# Sheet1.net
KiCad netlist of a schematic drawn in Altium Designer
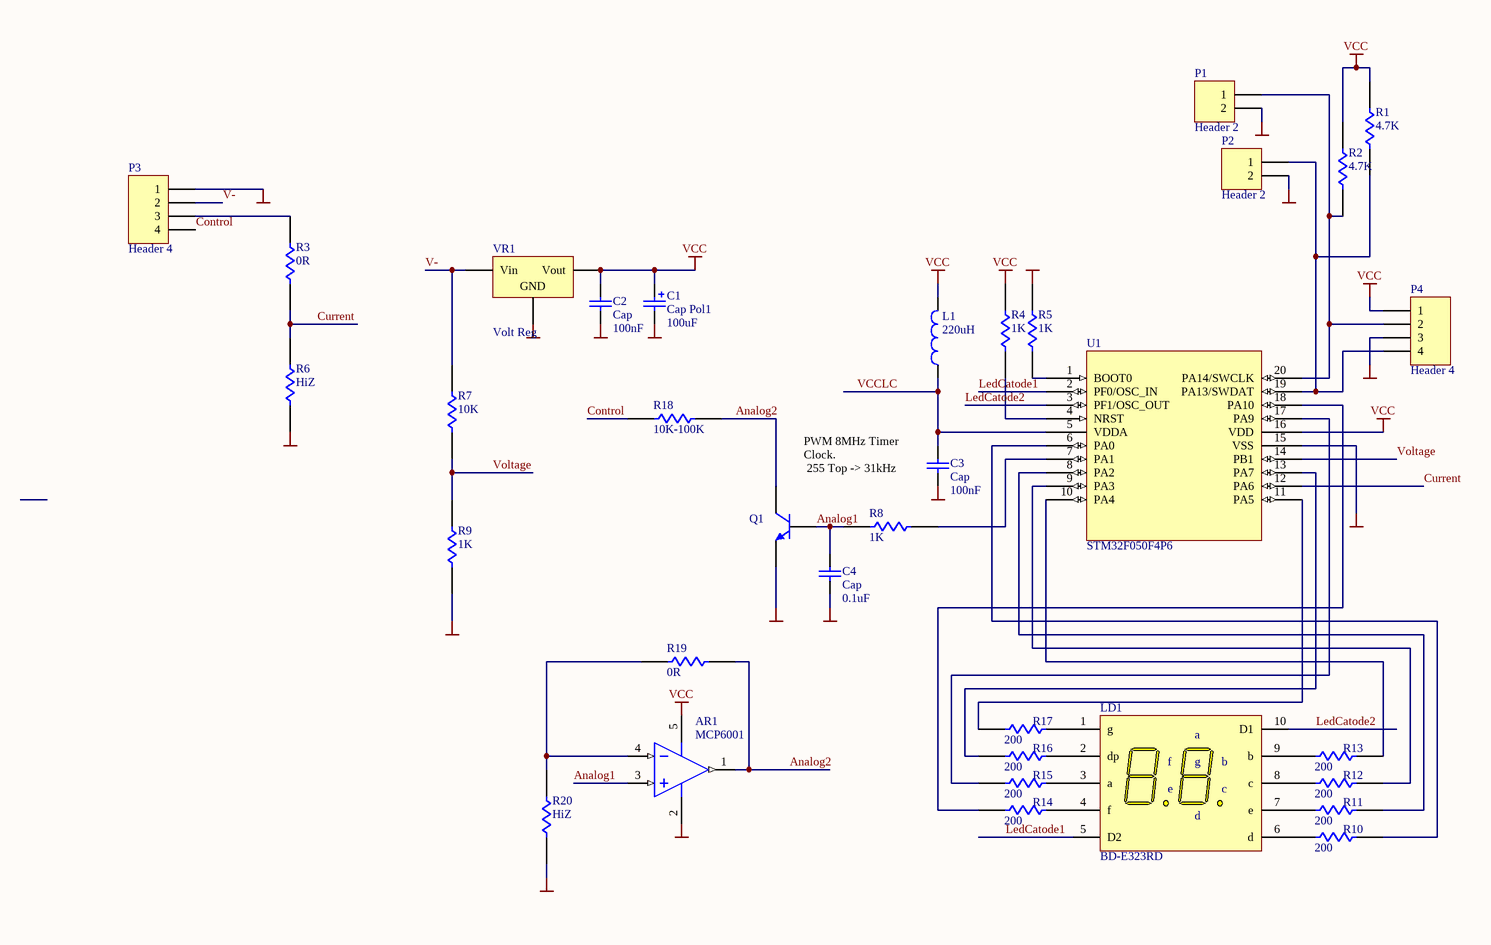
[diagram p0: Sheet1.SchDoc]

(export (version "E")
  (design (tool "Eeschema 10.0.6"))
  (components
    (comp (ref "AR1")
      (value "MCP6001")
      (footprint "SOT23-5_M")
      (description "FET Operational Amplifier")
      (fields (field (name "PUBLISHER") "Altium Limited"))
      (libsource (lib "Project") (part "MCP6001"))
    )
    (comp (ref "C1")
      (value "Cap Pol1")
      (footprint "RAD-0.3")
      (description "Polarized Capacitor (Radial)")
      (fields (field (name "ALTIUM_VALUE") "100uF") (field (name "PUBLISHER") "Altium Limited"))
      (libsource (lib "Project") (part "Cap Pol1"))
    )
    (comp (ref "C2")
      (value "Cap")
      (footprint "6-0805_M")
      (description "Capacitor")
      (fields (field (name "ALTIUM_VALUE") "100nF") (field (name "PUBLISHER") "Altium Limited"))
      (libsource (lib "Project") (part "Cap"))
    )
    (comp (ref "C3")
      (value "Cap")
      (footprint "6-0805_M")
      (description "Capacitor")
      (fields (field (name "ALTIUM_VALUE") "100nF") (field (name "PUBLISHER") "Altium Limited"))
      (libsource (lib "Project") (part "Cap"))
    )
    (comp (ref "C4")
      (value "Cap")
      (footprint "6-0805_M")
      (description "Capacitor")
      (fields (field (name "ALTIUM_VALUE") "0.1uF") (field (name "PUBLISHER") "Altium Limited"))
      (libsource (lib "Project") (part "Cap"))
    )
    (comp (ref "L1")
      (value "220uH")
      (footprint "INDC4532")
      (description "Inductor")
      (fields (field (name "PUBLISHER") "Altium Limited"))
      (libsource (lib "Project") (part "Inductor"))
    )
    (comp (ref "LD1") (value "BD-E323RD") (footprint "DD-04") (libsource (lib "Project") (part "BD-E323RD")))
    (comp (ref "P1")
      (value "Header 2")
      (footprint "HDR1X2")
      (description "Header, 2-Pin")
      (fields (field (name "PUBLISHER") "Altium Limited"))
      (libsource (lib "Miscellaneous Connectors") (part "Header 2"))
    )
    (comp (ref "P2")
      (value "Header 2")
      (footprint "HDR1X2")
      (description "Header, 2-Pin")
      (fields (field (name "PUBLISHER") "Altium Limited"))
      (libsource (lib "Miscellaneous Connectors") (part "Header 2"))
    )
    (comp (ref "P3")
      (value "Header 4")
      (footprint "HDR1X4")
      (description "Header, 4-Pin")
      (fields (field (name "PUBLISHER") "Altium Limited"))
      (libsource (lib "") (part "Header 4_1"))
    )
    (comp (ref "P4")
      (value "Header 4")
      (footprint "HDR1X4")
      (description "Header, 4-Pin")
      (fields (field (name "PUBLISHER") "Altium Limited"))
      (libsource (lib "Miscellaneous Connectors") (part "Header 4"))
    )
    (comp (ref "Q1")
      (value "NPN_SIGNAL")
      (footprint "SOT23_M")
      (description "Low power NPN transistor")
      (libsource (lib "Project") (part "NPN_SIGNAL"))
    )
    (comp (ref "R1")
      (value "4.7K")
      (footprint "6-0805_M")
      (fields (field (name "PUBLISHER") "Altium Limited"))
      (libsource (lib "Project") (part "Resistor"))
    )
    (comp (ref "R2")
      (value "4.7K")
      (footprint "6-0805_M")
      (fields (field (name "PUBLISHER") "Altium Limited"))
      (libsource (lib "Project") (part "Resistor"))
    )
    (comp (ref "R3")
      (value "0R")
      (footprint "6-0805_M")
      (fields (field (name "PUBLISHER") "Altium Limited"))
      (libsource (lib "Project") (part "Resistor"))
    )
    (comp (ref "R4")
      (value "1K")
      (footprint "6-0805_M")
      (fields (field (name "PUBLISHER") "Altium Limited"))
      (libsource (lib "Project") (part "Resistor"))
    )
    (comp (ref "R5")
      (value "1K")
      (footprint "6-0805_M")
      (fields (field (name "PUBLISHER") "Altium Limited"))
      (libsource (lib "Project") (part "Resistor"))
    )
    (comp (ref "R6")
      (value "HiZ")
      (footprint "6-0805_M")
      (fields (field (name "PUBLISHER") "Altium Limited"))
      (libsource (lib "Project") (part "Resistor"))
    )
    (comp (ref "R7")
      (value "10K")
      (footprint "6-0805_M")
      (fields (field (name "PUBLISHER") "Altium Limited"))
      (libsource (lib "Project") (part "Resistor"))
    )
    (comp (ref "R8")
      (value "1K")
      (footprint "6-0805_M")
      (fields (field (name "PUBLISHER") "Altium Limited"))
      (libsource (lib "Project") (part "Resistor"))
    )
    (comp (ref "R9")
      (value "1K")
      (footprint "6-0805_M")
      (fields (field (name "PUBLISHER") "Altium Limited"))
      (libsource (lib "Project") (part "Resistor"))
    )
    (comp (ref "R10")
      (value "200")
      (footprint "6-0805_M")
      (fields (field (name "PUBLISHER") "Altium Limited"))
      (libsource (lib "Project") (part "Resistor"))
    )
    (comp (ref "R11")
      (value "200")
      (footprint "6-0805_M")
      (fields (field (name "PUBLISHER") "Altium Limited"))
      (libsource (lib "Project") (part "Resistor"))
    )
    (comp (ref "R12")
      (value "200")
      (footprint "6-0805_M")
      (fields (field (name "PUBLISHER") "Altium Limited"))
      (libsource (lib "Project") (part "Resistor"))
    )
    (comp (ref "R13")
      (value "200")
      (footprint "6-0805_M")
      (fields (field (name "PUBLISHER") "Altium Limited"))
      (libsource (lib "Project") (part "Resistor"))
    )
    (comp (ref "R14")
      (value "200")
      (footprint "6-0805_M")
      (fields (field (name "PUBLISHER") "Altium Limited"))
      (libsource (lib "Project") (part "Resistor"))
    )
    (comp (ref "R15")
      (value "200")
      (footprint "6-0805_M")
      (fields (field (name "PUBLISHER") "Altium Limited"))
      (libsource (lib "Project") (part "Resistor"))
    )
    (comp (ref "R16")
      (value "200")
      (footprint "6-0805_M")
      (fields (field (name "PUBLISHER") "Altium Limited"))
      (libsource (lib "Project") (part "Resistor"))
    )
    (comp (ref "R17")
      (value "200")
      (footprint "6-0805_M")
      (fields (field (name "PUBLISHER") "Altium Limited"))
      (libsource (lib "Project") (part "Resistor"))
    )
    (comp (ref "R18")
      (value "10K-100K")
      (footprint "6-0805_M")
      (fields (field (name "PUBLISHER") "Altium Limited"))
      (libsource (lib "Project") (part "Resistor"))
    )
    (comp (ref "R19")
      (value "0R")
      (footprint "6-0805_M")
      (fields (field (name "PUBLISHER") "Altium Limited"))
      (libsource (lib "Project") (part "Resistor"))
    )
    (comp (ref "R20")
      (value "HiZ")
      (footprint "6-0805_M")
      (fields (field (name "PUBLISHER") "Altium Limited"))
      (libsource (lib "Project") (part "Resistor"))
    )
    (comp (ref "U1")
      (value "STM32F050F4P6")
      (footprint "TSOP20")
      (description "STM32 ARM-based 32-bit MCU with 16 Kbytes Flash, 20-pin")
      (fields (field (name "PUBLISHER") "Altium Limited"))
      (libsource (lib "Project") (part "STM32F050F4P6"))
    )
    (comp (ref "VR1")
      (value "Volt Reg")
      (footprint "DPAK")
      (description "Voltage Regulator")
      (fields (field (name "PUBLISHER") "Altium Limited"))
      (libsource (lib "Project") (part "Volt Reg"))
    )
  )
  (nets
    (net (code "1") (name "/Analog1") (class "Default")
      (node (ref "AR1") (pin "3") (pinfunction "IN+_3") (pintype "input"))
      (node (ref "C4") (pin "2") (pinfunction "2_2") (pintype "passive"))
      (node (ref "Q1") (pin "1") (pinfunction "B_1") (pintype "passive"))
      (node (ref "R8") (pin "1") (pinfunction "1_1") (pintype "passive"))
    )
    (net (code "2") (name "/Analog2") (class "Default")
      (node (ref "AR1") (pin "1") (pinfunction "OUT_1") (pintype "output"))
      (node (ref "Q1") (pin "3") (pinfunction "C_3") (pintype "passive"))
      (node (ref "R18") (pin "2") (pinfunction "2_2") (pintype "passive"))
      (node (ref "R19") (pin "2") (pinfunction "2_2") (pintype "passive"))
    )
    (net (code "3") (name "/Control") (class "Default")
      (node (ref "P3") (pin "4") (pinfunction "4_4") (pintype "passive"))
      (node (ref "R18") (pin "1") (pinfunction "1_1") (pintype "passive"))
    )
    (net (code "4") (name "/Current") (class "Default")
      (node (ref "R3") (pin "2") (pinfunction "2_2") (pintype "passive"))
      (node (ref "R6") (pin "1") (pinfunction "1_1") (pintype "passive"))
      (node (ref "U1") (pin "12") (pinfunction "PA6_12") (pintype "bidirectional"))
    )
    (net (code "5") (name "/LedCatode1") (class "Default")
      (node (ref "LD1") (pin "5") (pinfunction "D2_5") (pintype "passive"))
      (node (ref "U1") (pin "2") (pinfunction "PF0/OSC_IN_2") (pintype "bidirectional"))
    )
    (net (code "6") (name "/LedCatode2") (class "Default")
      (node (ref "LD1") (pin "10") (pinfunction "D1_10") (pintype "passive"))
      (node (ref "U1") (pin "3") (pinfunction "PF1/OSC_OUT_3") (pintype "bidirectional"))
    )
    (net (code "7") (name "/V-") (class "Default")
      (node (ref "P3") (pin "2") (pinfunction "2_2") (pintype "passive"))
      (node (ref "R7") (pin "1") (pinfunction "1_1") (pintype "passive"))
      (node (ref "VR1") (pin "1") (pinfunction "Vin_1") (pintype "passive"))
    )
    (net (code "8") (name "/VCCLC") (class "Default")
      (node (ref "C3") (pin "2") (pinfunction "2_2") (pintype "passive"))
      (node (ref "L1") (pin "1") (pinfunction "1_1") (pintype "passive"))
      (node (ref "U1") (pin "5") (pinfunction "VDDA_5") (pintype "power_in"))
    )
    (net (code "9") (name "/Voltage") (class "Default")
      (node (ref "R7") (pin "2") (pinfunction "2_2") (pintype "passive"))
      (node (ref "R9") (pin "1") (pinfunction "1_1") (pintype "passive"))
      (node (ref "U1") (pin "14") (pinfunction "PB1_14") (pintype "bidirectional"))
    )
    (net (code "10") (name "GND") (class "Default")
      (node (ref "AR1") (pin "2") (pinfunction "GND_2") (pintype "power_in"))
      (node (ref "C1") (pin "2") (pinfunction "2_2") (pintype "passive"))
      (node (ref "C2") (pin "1") (pinfunction "1_1") (pintype "passive"))
      (node (ref "C3") (pin "1") (pinfunction "1_1") (pintype "passive"))
      (node (ref "C4") (pin "1") (pinfunction "1_1") (pintype "passive"))
      (node (ref "P1") (pin "2") (pinfunction "2_2") (pintype "passive"))
      (node (ref "P2") (pin "2") (pinfunction "2_2") (pintype "passive"))
      (node (ref "P3") (pin "1") (pinfunction "1_1") (pintype "passive"))
      (node (ref "P4") (pin "3") (pinfunction "3_3") (pintype "passive"))
      (node (ref "Q1") (pin "2") (pinfunction "E_2") (pintype "passive"))
      (node (ref "R20") (pin "1") (pinfunction "1_1") (pintype "passive"))
      (node (ref "R5") (pin "1") (pinfunction "1_1") (pintype "passive"))
      (node (ref "R6") (pin "2") (pinfunction "2_2") (pintype "passive"))
      (node (ref "R9") (pin "2") (pinfunction "2_2") (pintype "passive"))
      (node (ref "U1") (pin "15") (pinfunction "VSS_15") (pintype "power_in"))
      (node (ref "VR1") (pin "2") (pinfunction "GND_2") (pintype "passive"))
    )
    (net (code "11") (name "Net-(AR1-IN-)") (class "Default")
      (node (ref "AR1") (pin "4") (pinfunction "IN-_4") (pintype "input"))
      (node (ref "R19") (pin "1") (pinfunction "1_1") (pintype "passive"))
      (node (ref "R20") (pin "2") (pinfunction "2_2") (pintype "passive"))
    )
    (net (code "12") (name "Net-(LD1-a)") (class "Default")
      (node (ref "LD1") (pin "3") (pinfunction "a_3") (pintype "passive"))
      (node (ref "R15") (pin "2") (pinfunction "2_2") (pintype "passive"))
    )
    (net (code "13") (name "Net-(LD1-b)") (class "Default")
      (node (ref "LD1") (pin "9") (pinfunction "b_9") (pintype "passive"))
      (node (ref "R13") (pin "1") (pinfunction "1_1") (pintype "passive"))
    )
    (net (code "14") (name "Net-(LD1-c)") (class "Default")
      (node (ref "LD1") (pin "8") (pinfunction "c_8") (pintype "passive"))
      (node (ref "R12") (pin "1") (pinfunction "1_1") (pintype "passive"))
    )
    (net (code "15") (name "Net-(LD1-d)") (class "Default")
      (node (ref "LD1") (pin "6") (pinfunction "d_6") (pintype "passive"))
      (node (ref "R10") (pin "1") (pinfunction "1_1") (pintype "passive"))
    )
    (net (code "16") (name "Net-(LD1-dp)") (class "Default")
      (node (ref "LD1") (pin "2") (pinfunction "dp_2") (pintype "passive"))
      (node (ref "R16") (pin "2") (pinfunction "2_2") (pintype "passive"))
    )
    (net (code "17") (name "Net-(LD1-e)") (class "Default")
      (node (ref "LD1") (pin "7") (pinfunction "e_7") (pintype "passive"))
      (node (ref "R11") (pin "1") (pinfunction "1_1") (pintype "passive"))
    )
    (net (code "18") (name "Net-(LD1-f)") (class "Default")
      (node (ref "LD1") (pin "4") (pinfunction "f_4") (pintype "passive"))
      (node (ref "R14") (pin "2") (pinfunction "2_2") (pintype "passive"))
    )
    (net (code "19") (name "Net-(LD1-g)") (class "Default")
      (node (ref "LD1") (pin "1") (pinfunction "g_1") (pintype "passive"))
      (node (ref "R17") (pin "2") (pinfunction "2_2") (pintype "passive"))
    )
    (net (code "20") (name "Net-(P3-Pad3)") (class "Default")
      (node (ref "P3") (pin "3") (pinfunction "3_3") (pintype "passive"))
      (node (ref "R3") (pin "1") (pinfunction "1_1") (pintype "passive"))
    )
    (net (code "21") (name "Net-(U1-BOOT0)") (class "Default")
      (node (ref "R5") (pin "2") (pinfunction "2_2") (pintype "passive"))
      (node (ref "U1") (pin "1") (pinfunction "BOOT0_1") (pintype "input"))
    )
    (net (code "22") (name "Net-(U1-NRST)") (class "Default")
      (node (ref "R4") (pin "2") (pinfunction "2_2") (pintype "passive"))
      (node (ref "U1") (pin "4") (pinfunction "NRST_4") (pintype "input"))
    )
    (net (code "23") (name "Net-(U1-PA0)") (class "Default")
      (node (ref "R10") (pin "2") (pinfunction "2_2") (pintype "passive"))
      (node (ref "U1") (pin "6") (pinfunction "PA0_6") (pintype "bidirectional"))
    )
    (net (code "24") (name "Net-(U1-PA1)") (class "Default")
      (node (ref "R8") (pin "2") (pinfunction "2_2") (pintype "passive"))
      (node (ref "U1") (pin "7") (pinfunction "PA1_7") (pintype "bidirectional"))
    )
    (net (code "25") (name "Net-(U1-PA2)") (class "Default")
      (node (ref "R11") (pin "2") (pinfunction "2_2") (pintype "passive"))
      (node (ref "U1") (pin "8") (pinfunction "PA2_8") (pintype "bidirectional"))
    )
    (net (code "26") (name "Net-(U1-PA3)") (class "Default")
      (node (ref "R12") (pin "2") (pinfunction "2_2") (pintype "passive"))
      (node (ref "U1") (pin "9") (pinfunction "PA3_9") (pintype "bidirectional"))
    )
    (net (code "27") (name "Net-(U1-PA4)") (class "Default")
      (node (ref "R13") (pin "2") (pinfunction "2_2") (pintype "passive"))
      (node (ref "U1") (pin "10") (pinfunction "PA4_10") (pintype "bidirectional"))
    )
    (net (code "28") (name "Net-(U1-PA5)") (class "Default")
      (node (ref "R17") (pin "1") (pinfunction "1_1") (pintype "passive"))
      (node (ref "U1") (pin "11") (pinfunction "PA5_11") (pintype "bidirectional"))
    )
    (net (code "29") (name "Net-(U1-PA7)") (class "Default")
      (node (ref "R16") (pin "1") (pinfunction "1_1") (pintype "passive"))
      (node (ref "U1") (pin "13") (pinfunction "PA7_13") (pintype "bidirectional"))
    )
    (net (code "30") (name "Net-(U1-PA9)") (class "Default")
      (node (ref "R15") (pin "1") (pinfunction "1_1") (pintype "passive"))
      (node (ref "U1") (pin "17") (pinfunction "PA9_17") (pintype "bidirectional"))
    )
    (net (code "31") (name "Net-(U1-PA10)") (class "Default")
      (node (ref "R14") (pin "1") (pinfunction "1_1") (pintype "passive"))
      (node (ref "U1") (pin "18") (pinfunction "PA10_18") (pintype "bidirectional"))
    )
    (net (code "32") (name "Net-(U1-PA13{slash}SWDAT)") (class "Default")
      (node (ref "P2") (pin "1") (pinfunction "1_1") (pintype "passive"))
      (node (ref "P4") (pin "4") (pinfunction "4_4") (pintype "passive"))
      (node (ref "R1") (pin "2") (pinfunction "2_2") (pintype "passive"))
      (node (ref "U1") (pin "19") (pinfunction "PA13/SWDAT_19") (pintype "bidirectional"))
    )
    (net (code "33") (name "Net-(U1-PA14{slash}SWCLK)") (class "Default")
      (node (ref "P1") (pin "1") (pinfunction "1_1") (pintype "passive"))
      (node (ref "P4") (pin "2") (pinfunction "2_2") (pintype "passive"))
      (node (ref "R2") (pin "2") (pinfunction "2_2") (pintype "passive"))
      (node (ref "U1") (pin "20") (pinfunction "PA14/SWCLK_20") (pintype "bidirectional"))
    )
    (net (code "34") (name "VCC") (class "Default")
      (node (ref "AR1") (pin "5") (pinfunction "V+_5") (pintype "power_in"))
      (node (ref "C1") (pin "1") (pinfunction "1_1") (pintype "passive"))
      (node (ref "C2") (pin "2") (pinfunction "2_2") (pintype "passive"))
      (node (ref "L1") (pin "2") (pinfunction "2_2") (pintype "passive"))
      (node (ref "P4") (pin "1") (pinfunction "1_1") (pintype "passive"))
      (node (ref "R1") (pin "1") (pinfunction "1_1") (pintype "passive"))
      (node (ref "R2") (pin "1") (pinfunction "1_1") (pintype "passive"))
      (node (ref "R4") (pin "1") (pinfunction "1_1") (pintype "passive"))
      (node (ref "U1") (pin "16") (pinfunction "VDD_16") (pintype "power_in"))
      (node (ref "VR1") (pin "3") (pinfunction "Vout_3") (pintype "passive"))
    )
  )
)
